# Sparkman_v1.net
KiCad netlist of a schematic drawn in EAGLE
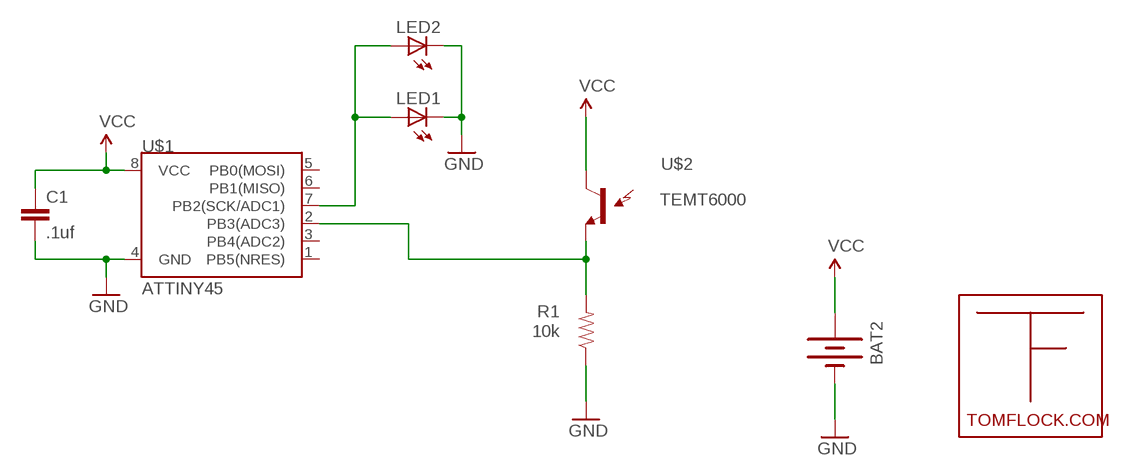
[diagram p0: schematic, sheet 1]

(export (version "E")
  (design (tool "Eeschema 10.0.6"))
  (components
    (comp (ref "BAT2")
      (value "BATTERY12MM")
      (footprint "eagle-import:BATTCON_12MM")
      (libsource (lib "eagle-import") (part "BATTERY12MM"))
    )
    (comp (ref "C1")
      (value ".1uf")
      (footprint "eagle-import:0603-CAP")
      (libsource (lib "eagle-import") (part "CAP0603-CAP"))
    )
    (comp (ref "LED1")
      (value "LED0603")
      (footprint "eagle-import:LED-0603")
      (libsource (lib "eagle-import") (part "LED0603"))
    )
    (comp (ref "LED2")
      (value "LED0603")
      (footprint "eagle-import:LED-0603")
      (libsource (lib "eagle-import") (part "LED0603"))
    )
    (comp (ref "R1")
      (value "10k")
      (footprint "eagle-import:0603-RES")
      (libsource (lib "eagle-import") (part "RESISTOR0603-RES"))
    )
    (comp (ref "U$1")
      (value "ATTINY45")
      (footprint "eagle-import:SO08-EIAJ")
      (libsource (lib "eagle-import") (part "ATTINY45"))
    )
    (comp (ref "U$2")
      (value "TEMT6000")
      (footprint "eagle-import:TEMT6000-SEN")
      (libsource (lib "eagle-import") (part "TEMT6000"))
    )
    (comp (ref "U$3")
      (value "TFLOGO")
      (footprint "eagle-import:TFLOGO")
      (libsource (lib "eagle-import") (part "TFLOGO"))
    )
  )
  (nets
    (net (code "1") (name "GND") (class "Default")
      (node (ref "BAT2") (pin "GND") (pinfunction "-_GND") (pintype "power_in"))
      (node (ref "C1") (pin "2") (pinfunction "2_2") (pintype "passive"))
      (node (ref "LED1") (pin "C") (pinfunction "C_C") (pintype "passive"))
      (node (ref "LED2") (pin "C") (pinfunction "C_C") (pintype "passive"))
      (node (ref "R1") (pin "1") (pinfunction "1_1") (pintype "passive"))
      (node (ref "U$1") (pin "4") (pinfunction "GND_4") (pintype "bidirectional"))
    )
    (net (code "2") (name "Net-(U$1-PB2(SCK{slash}ADC1))") (class "Default")
      (node (ref "LED1") (pin "A") (pinfunction "A_A") (pintype "passive"))
      (node (ref "LED2") (pin "A") (pinfunction "A_A") (pintype "passive"))
      (node (ref "U$1") (pin "7") (pinfunction "PB2(SCK/ADC1)_7") (pintype "bidirectional"))
    )
    (net (code "3") (name "Net-(U$1-PB3(ADC3))") (class "Default")
      (node (ref "R1") (pin "2") (pinfunction "2_2") (pintype "passive"))
      (node (ref "U$1") (pin "2") (pinfunction "PB3(ADC3)_2") (pintype "bidirectional"))
      (node (ref "U$2") (pin "EMITTER") (pinfunction "E1_EMITTER") (pintype "passive"))
    )
    (net (code "4") (name "VCC") (class "Default")
      (node (ref "BAT2") (pin "PWR@1") (pinfunction "+_PWR@1") (pintype "power_in"))
      (node (ref "C1") (pin "1") (pinfunction "1_1") (pintype "passive"))
      (node (ref "U$1") (pin "8") (pinfunction "VCC_8") (pintype "bidirectional"))
      (node (ref "U$2") (pin "COLLECTOR") (pinfunction "C1_COLLECTOR") (pintype "passive"))
    )
    (net (code "5") (name "unconnected-(U$1-PB0(MOSI)-Pad5)") (class "Default")
      (node (ref "U$1") (pin "5") (pinfunction "PB0(MOSI)_5") (pintype "bidirectional"))
    )
    (net (code "6") (name "unconnected-(U$1-PB1(MISO)-Pad6)") (class "Default")
      (node (ref "U$1") (pin "6") (pinfunction "PB1(MISO)_6") (pintype "bidirectional"))
    )
    (net (code "7") (name "unconnected-(U$1-PB4(ADC2)-Pad3)") (class "Default")
      (node (ref "U$1") (pin "3") (pinfunction "PB4(ADC2)_3") (pintype "bidirectional"))
    )
    (net (code "8") (name "unconnected-(U$1-PB5(NRES)-Pad1)") (class "Default")
      (node (ref "U$1") (pin "1") (pinfunction "PB5(NRES)_1") (pintype "bidirectional"))
    )
  )
)
